# hand_r1.net
KiCad netlist of a schematic drawn in EAGLE
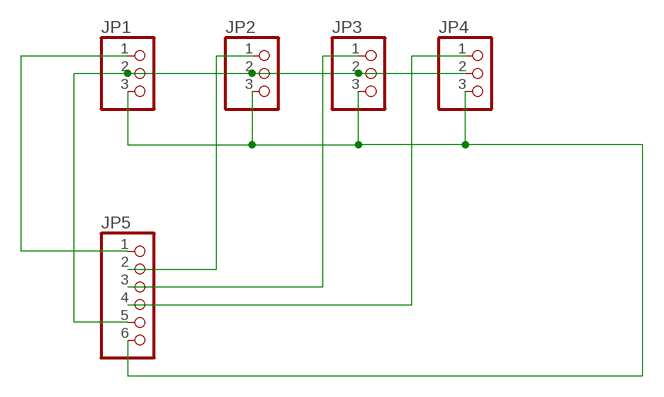
[diagram p0: schematic, sheet 1]

(export (version "E")
  (design (tool "Eeschema 10.0.6"))
  (components
    (comp (ref "JP1")
      (value "PINHD-1X3")
      (footprint "eagle-import:1X03")
      (libsource (lib "eagle-import") (part "PINHD-1X3"))
    )
    (comp (ref "JP2")
      (value "PINHD-1X3")
      (footprint "eagle-import:1X03")
      (libsource (lib "eagle-import") (part "PINHD-1X3"))
    )
    (comp (ref "JP3")
      (value "PINHD-1X3")
      (footprint "eagle-import:1X03")
      (libsource (lib "eagle-import") (part "PINHD-1X3"))
    )
    (comp (ref "JP4")
      (value "PINHD-1X3")
      (footprint "eagle-import:1X03")
      (libsource (lib "eagle-import") (part "PINHD-1X3"))
    )
    (comp (ref "JP5")
      (value "PINHD-1X6")
      (footprint "eagle-import:1X06")
      (libsource (lib "eagle-import") (part "PINHD-1X6"))
    )
  )
  (nets
    (net (code "1") (name "Net-(JP1-Pad1)") (class "Default")
      (node (ref "JP1") (pin "1") (pinfunction "1_1") (pintype "passive"))
      (node (ref "JP5") (pin "1") (pinfunction "1_1") (pintype "passive"))
    )
    (net (code "2") (name "Net-(JP1-Pad2)") (class "Default")
      (node (ref "JP1") (pin "2") (pinfunction "2_2") (pintype "passive"))
      (node (ref "JP2") (pin "2") (pinfunction "2_2") (pintype "passive"))
      (node (ref "JP3") (pin "2") (pinfunction "2_2") (pintype "passive"))
      (node (ref "JP4") (pin "2") (pinfunction "2_2") (pintype "passive"))
      (node (ref "JP5") (pin "5") (pinfunction "5_5") (pintype "passive"))
    )
    (net (code "3") (name "Net-(JP1-Pad3)") (class "Default")
      (node (ref "JP1") (pin "3") (pinfunction "3_3") (pintype "passive"))
      (node (ref "JP2") (pin "3") (pinfunction "3_3") (pintype "passive"))
      (node (ref "JP3") (pin "3") (pinfunction "3_3") (pintype "passive"))
      (node (ref "JP4") (pin "3") (pinfunction "3_3") (pintype "passive"))
      (node (ref "JP5") (pin "6") (pinfunction "6_6") (pintype "passive"))
    )
    (net (code "4") (name "Net-(JP2-Pad1)") (class "Default")
      (node (ref "JP2") (pin "1") (pinfunction "1_1") (pintype "passive"))
      (node (ref "JP5") (pin "2") (pinfunction "2_2") (pintype "passive"))
    )
    (net (code "5") (name "Net-(JP3-Pad1)") (class "Default")
      (node (ref "JP3") (pin "1") (pinfunction "1_1") (pintype "passive"))
      (node (ref "JP5") (pin "3") (pinfunction "3_3") (pintype "passive"))
    )
    (net (code "6") (name "Net-(JP4-Pad1)") (class "Default")
      (node (ref "JP4") (pin "1") (pinfunction "1_1") (pintype "passive"))
      (node (ref "JP5") (pin "4") (pinfunction "4_4") (pintype "passive"))
    )
  )
)
